# 5_spi_memory.net
KiCad netlist of a schematic drawn in Altium Designer
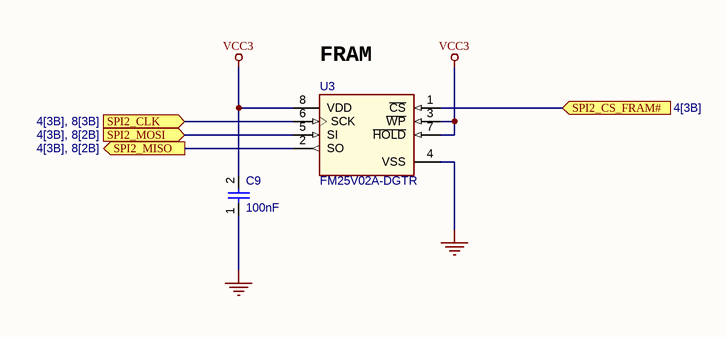
[diagram p0: 5_spi_memory.SchDoc]

(export (version "E")
  (design (tool "Eeschema 10.0.6"))
  (components
    (comp (ref "C9")
      (value "100nF")
      (footprint "CAPC0402(1005)60_L")
      (description "Chip Capacitor, 100nF +/-20%, 10V, 0402, Thickness 0.6 mm")
      (fields (field (name "TOLERANCE") "20%") (field (name "Comment") "Capacitor 100nF +/-20% 10V 0402"))
      (libsource (lib "<Company> Server") (part "CAP-NP-2"))
    )
    (comp (ref "U3")
      (value "FM25V02A-DGTR")
      (footprint "SON95P400X75_HS-9N")
      (description "REEL / F-RAM Memory Serial")
      (libsource (lib "<Company> Server") (part "CMP-019-00000-4"))
    )
  )
  (nets
    (net (code "1") (name "/SPI2_CLK") (class "Default")
      (node (ref "U3") (pin "6") (pinfunction "SCK_6") (pintype "input"))
    )
    (net (code "2") (name "/SPI2_CS_FRAM#") (class "Default")
      (node (ref "U3") (pin "1") (pinfunction "~{CS}_1") (pintype "input"))
    )
    (net (code "3") (name "/SPI2_MISO") (class "Default")
      (node (ref "U3") (pin "2") (pinfunction "SO_2") (pintype "output"))
    )
    (net (code "4") (name "/SPI2_MOSI") (class "Default")
      (node (ref "U3") (pin "5") (pinfunction "SI_5") (pintype "input"))
    )
    (net (code "5") (name "GND") (class "Default")
      (node (ref "C9") (pin "1") (pinfunction "1_1") (pintype "passive"))
      (node (ref "U3") (pin "4") (pinfunction "VSS_4") (pintype "power_in"))
    )
    (net (code "6") (name "VCC3") (class "Default")
      (node (ref "C9") (pin "2") (pinfunction "2_2") (pintype "passive"))
      (node (ref "U3") (pin "3") (pinfunction "~{WP}_3") (pintype "input"))
      (node (ref "U3") (pin "7") (pinfunction "~{HOLD}_7") (pintype "input"))
      (node (ref "U3") (pin "8") (pinfunction "VDD_8") (pintype "power_in"))
    )
  )
)
